# Sheet2.net
KiCad netlist of a schematic drawn in Altium Designer
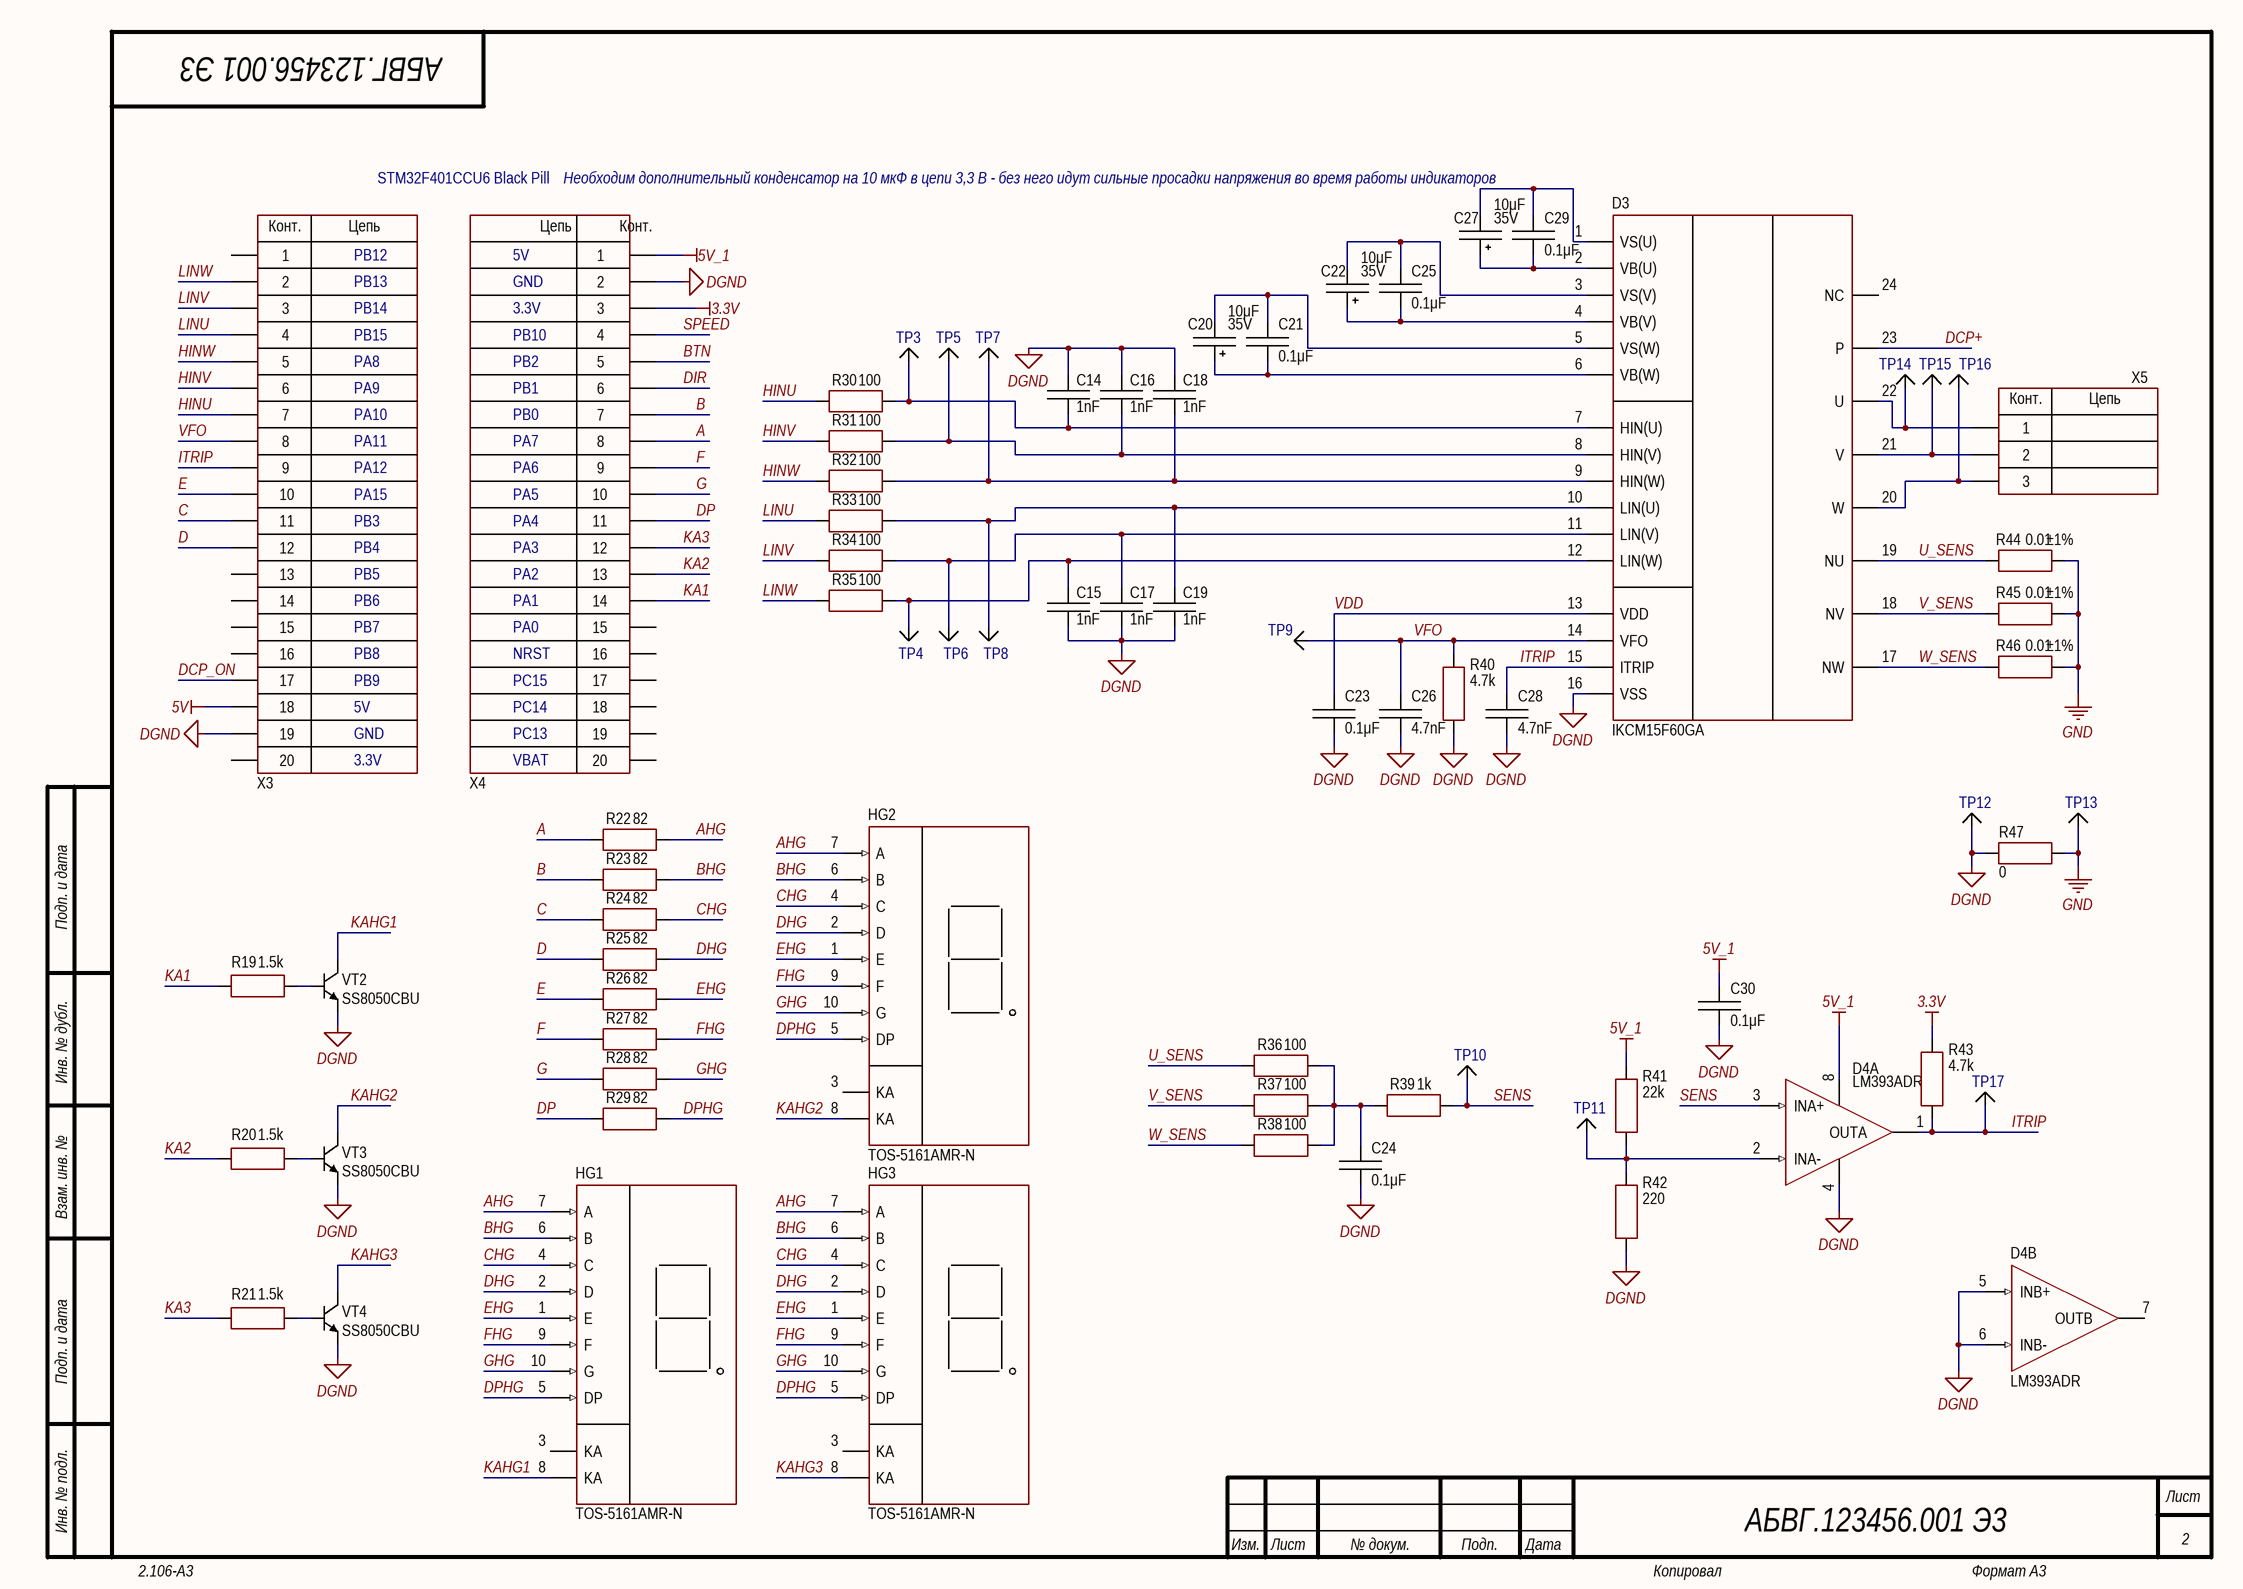
[diagram p0: Sheet2.SchDoc]

(export (version "E")
  (design (tool "Eeschema 10.0.6"))
  (components
    (comp (ref "C14")
      (value "1nF")
      (footprint "CAP: 1206")
      (fields
        (field (name "PARTNUMBER") "Ceramic capacitor, 1nF,   50V")
        (field (name "VALUEMANUFACTURERPARTNUMBER") "Ceramic capacitor, 1nF, X7R, ±10%, 50V, 1206, -55...+125°C")
        (field (name "TOLERANCE") "±10%")
      )
      (libsource (lib "capacitor") (part "Ceramic_1206"))
    )
    (comp (ref "C15")
      (value "1nF")
      (footprint "CAP: 1206")
      (fields
        (field (name "PARTNUMBER") "Ceramic capacitor, 1nF,   50V")
        (field (name "VALUEMANUFACTURERPARTNUMBER") "Ceramic capacitor, 1nF, X7R, ±10%, 50V, 1206, -55...+125°C")
        (field (name "TOLERANCE") "±10%")
      )
      (libsource (lib "capacitor") (part "Ceramic_1206"))
    )
    (comp (ref "C16")
      (value "1nF")
      (footprint "CAP: 1206")
      (fields
        (field (name "PARTNUMBER") "Ceramic capacitor, 1nF,   50V")
        (field (name "VALUEMANUFACTURERPARTNUMBER") "Ceramic capacitor, 1nF, X7R, ±10%, 50V, 1206, -55...+125°C")
        (field (name "TOLERANCE") "±10%")
      )
      (libsource (lib "capacitor") (part "Ceramic_1206"))
    )
    (comp (ref "C17")
      (value "1nF")
      (footprint "CAP: 1206")
      (fields
        (field (name "PARTNUMBER") "Ceramic capacitor, 1nF,   50V")
        (field (name "VALUEMANUFACTURERPARTNUMBER") "Ceramic capacitor, 1nF, X7R, ±10%, 50V, 1206, -55...+125°C")
        (field (name "TOLERANCE") "±10%")
      )
      (libsource (lib "capacitor") (part "Ceramic_1206"))
    )
    (comp (ref "C18")
      (value "1nF")
      (footprint "CAP: 1206")
      (fields
        (field (name "PARTNUMBER") "Ceramic capacitor, 1nF,   50V")
        (field (name "VALUEMANUFACTURERPARTNUMBER") "Ceramic capacitor, 1nF, X7R, ±10%, 50V, 1206, -55...+125°C")
        (field (name "TOLERANCE") "±10%")
      )
      (libsource (lib "capacitor") (part "Ceramic_1206"))
    )
    (comp (ref "C19")
      (value "1nF")
      (footprint "CAP: 1206")
      (fields
        (field (name "PARTNUMBER") "Ceramic capacitor, 1nF,   50V")
        (field (name "VALUEMANUFACTURERPARTNUMBER") "Ceramic capacitor, 1nF, X7R, ±10%, 50V, 1206, -55...+125°C")
        (field (name "TOLERANCE") "±10%")
      )
      (libsource (lib "capacitor") (part "Ceramic_1206"))
    )
    (comp (ref "C20")
      (value "10μF")
      (footprint "CAP: D5C2H11")
      (fields
        (field (name "MANUFACTURER") "?")
        (field (name "PARTNUMBER") "9000565842")
        (field (name "VALUEMANUFACTURERPARTNUMBER") "Aluminium capacitor, 10μF, 35V, ±20%, 54mOhm, ?, -40...+105°C")
        (field (name "VOLTAGE") "35V")
      )
      (libsource (lib "capacitor") (part "Aluminium"))
    )
    (comp (ref "C21")
      (value "0.1μF")
      (footprint "CAP: 1206")
      (fields
        (field (name "PARTNUMBER") "Ceramic capacitor, 0.1μF,   50V")
        (field (name "VALUEMANUFACTURERPARTNUMBER") "Ceramic capacitor, 0.1μF, X7R, ±10%, 50V, 1206, -55...+125°C")
        (field (name "TOLERANCE") "±10%")
      )
      (libsource (lib "capacitor") (part "Ceramic_1206"))
    )
    (comp (ref "C22")
      (value "10μF")
      (footprint "CAP: D5C2H11")
      (fields
        (field (name "MANUFACTURER") "?")
        (field (name "PARTNUMBER") "9000565842")
        (field (name "VALUEMANUFACTURERPARTNUMBER") "Aluminium capacitor, 10μF, 35V, ±20%, 54mOhm, ?, -40...+105°C")
        (field (name "VOLTAGE") "35V")
      )
      (libsource (lib "capacitor") (part "Aluminium"))
    )
    (comp (ref "C23")
      (value "0.1μF")
      (footprint "CAP: 1206")
      (fields
        (field (name "PARTNUMBER") "Ceramic capacitor, 0.1μF,   50V")
        (field (name "VALUEMANUFACTURERPARTNUMBER") "Ceramic capacitor, 0.1μF, X7R, ±10%, 50V, 1206, -55...+125°C")
        (field (name "TOLERANCE") "±10%")
      )
      (libsource (lib "capacitor") (part "Ceramic_1206"))
    )
    (comp (ref "C24")
      (value "0.1μF")
      (footprint "CAP: 1206")
      (fields
        (field (name "PARTNUMBER") "Ceramic capacitor, 0.1μF,   50V")
        (field (name "VALUEMANUFACTURERPARTNUMBER") "Ceramic capacitor, 0.1μF, X7R, ±10%, 50V, 1206, -55...+125°C")
        (field (name "TOLERANCE") "±10%")
      )
      (libsource (lib "capacitor") (part "Ceramic_1206"))
    )
    (comp (ref "C25")
      (value "0.1μF")
      (footprint "CAP: 1206")
      (fields
        (field (name "PARTNUMBER") "Ceramic capacitor, 0.1μF,   50V")
        (field (name "VALUEMANUFACTURERPARTNUMBER") "Ceramic capacitor, 0.1μF, X7R, ±10%, 50V, 1206, -55...+125°C")
        (field (name "TOLERANCE") "±10%")
      )
      (libsource (lib "capacitor") (part "Ceramic_1206"))
    )
    (comp (ref "C26")
      (value "4.7nF")
      (footprint "CAP: 1206")
      (fields
        (field (name "PARTNUMBER") "Ceramic capacitor, 4.7nF,   50V")
        (field (name "VALUEMANUFACTURERPARTNUMBER") "Ceramic capacitor, 4.7nF, X7R, ±10%, 50V, 1206, -55...+125°C")
        (field (name "TOLERANCE") "±10%")
      )
      (libsource (lib "capacitor") (part "Ceramic_1206"))
    )
    (comp (ref "C27")
      (value "10μF")
      (footprint "CAP: D5C2H11")
      (fields
        (field (name "MANUFACTURER") "?")
        (field (name "PARTNUMBER") "9000565842")
        (field (name "VALUEMANUFACTURERPARTNUMBER") "Aluminium capacitor, 10μF, 35V, ±20%, 54mOhm, ?, -40...+105°C")
        (field (name "VOLTAGE") "35V")
      )
      (libsource (lib "capacitor") (part "Aluminium"))
    )
    (comp (ref "C28")
      (value "4.7nF")
      (footprint "CAP: 1206")
      (fields
        (field (name "PARTNUMBER") "Ceramic capacitor, 4.7nF,   50V")
        (field (name "VALUEMANUFACTURERPARTNUMBER") "Ceramic capacitor, 4.7nF, X7R, ±10%, 50V, 1206, -55...+125°C")
        (field (name "TOLERANCE") "±10%")
      )
      (libsource (lib "capacitor") (part "Ceramic_1206"))
    )
    (comp (ref "C29")
      (value "0.1μF")
      (footprint "CAP: 1206")
      (fields
        (field (name "PARTNUMBER") "Ceramic capacitor, 0.1μF,   50V")
        (field (name "VALUEMANUFACTURERPARTNUMBER") "Ceramic capacitor, 0.1μF, X7R, ±10%, 50V, 1206, -55...+125°C")
        (field (name "TOLERANCE") "±10%")
      )
      (libsource (lib "capacitor") (part "Ceramic_1206"))
    )
    (comp (ref "C30")
      (value "0.1μF")
      (footprint "CAP: 1206")
      (fields
        (field (name "PARTNUMBER") "Ceramic capacitor, 0.1μF,   50V")
        (field (name "VALUEMANUFACTURERPARTNUMBER") "Ceramic capacitor, 0.1μF, X7R, ±10%, 50V, 1206, -55...+125°C")
        (field (name "TOLERANCE") "±10%")
      )
      (libsource (lib "capacitor") (part "Ceramic_1206"))
    )
    (comp (ref "D3")
      (value "~")
      (footprint "INF-CIPOS MINI")
      (description "Fully isolated Dual In-Line molded  IGBT module")
      (fields
        (field (name "MANUFACTURER") "INFINEON TECHNOLOGIES AG.")
        (field (name "VALUEMANUFACTURERPARTNUMBER") "600 V, 15 A three-phase intelligent power module, , , 15A, , 450V, -40...+125°C, IKCM15F60GA")
        (field (name "PARTNUMBER") "IKCM15F60GA")
      )
      (libsource (lib "ic-power-module") (part "IKCM15F60GA"))
    )
    (comp (ref "D4")
      (value "~")
      (footprint "8-SOIC")
      (description "Low Power Low Offset Voltage Dual Comparator")
      (fields
        (field (name "MANUFACTURER") "Maxim Integrated Products")
        (field (name "VALUEMANUFACTURERPARTNUMBER") "IC comparator, Rail-to-Rail, 2...36 V, ±1...±18 V, 0…70°C, SOP-8")
        (field (name "PARTNUMBER") "LM393ADR")
      )
      (libsource (lib "ic-comparator") (part "LM393ADR"))
    )
    (comp (ref "HG1")
      (value "~")
      (footprint "TOS-5161AMR-N")
      (description "Single Digit Display LED")
      (fields
        (field (name "MANUFACTURER") "Taiwan Oasis Technology Co., Ltd")
        (field (name "VALUEMANUFACTURERPARTNUMBER") "Single Digit Display LED, , -25...+85°C, TOS-5161AMR-N")
        (field (name "PARTNUMBER") "TOS-5161AMR-N")
      )
      (libsource (lib "indicator") (part "TOS-5161AMR-N"))
    )
    (comp (ref "HG2")
      (value "~")
      (footprint "TOS-5161AMR-N")
      (description "Single Digit Display LED")
      (fields
        (field (name "MANUFACTURER") "Taiwan Oasis Technology Co., Ltd")
        (field (name "VALUEMANUFACTURERPARTNUMBER") "Single Digit Display LED, , -25...+85°C, TOS-5161AMR-N")
        (field (name "PARTNUMBER") "TOS-5161AMR-N")
      )
      (libsource (lib "indicator") (part "TOS-5161AMR-N"))
    )
    (comp (ref "HG3")
      (value "~")
      (footprint "TOS-5161AMR-N")
      (description "Single Digit Display LED")
      (fields
        (field (name "MANUFACTURER") "Taiwan Oasis Technology Co., Ltd")
        (field (name "VALUEMANUFACTURERPARTNUMBER") "Single Digit Display LED, , -25...+85°C, TOS-5161AMR-N")
        (field (name "PARTNUMBER") "TOS-5161AMR-N")
      )
      (libsource (lib "indicator") (part "TOS-5161AMR-N"))
    )
    (comp (ref "R19")
      (value "1.5k")
      (footprint "RES: 1206")
      (fields
        (field (name "MANUFACTURER") "Yageo")
        (field (name "PARTNUMBER") "RC1206JR-07100RL")
        (field (name "VALUEMANUFACTURERPARTNUMBER") "Resistor film, 1.5k, ±5%, 1206, 0.25W, -55...+125°C")
      )
      (libsource (lib "resistor") (part "Resistor_1206"))
    )
    (comp (ref "R20")
      (value "1.5k")
      (footprint "RES: 1206")
      (fields
        (field (name "MANUFACTURER") "Yageo")
        (field (name "PARTNUMBER") "RC1206JR-07100RL")
        (field (name "VALUEMANUFACTURERPARTNUMBER") "Resistor film, 1.5k, ±5%, 1206, 0.25W, -55...+125°C")
      )
      (libsource (lib "resistor") (part "Resistor_1206"))
    )
    (comp (ref "R21")
      (value "1.5k")
      (footprint "RES: 1206")
      (fields
        (field (name "MANUFACTURER") "Yageo")
        (field (name "PARTNUMBER") "RC1206JR-07100RL")
        (field (name "VALUEMANUFACTURERPARTNUMBER") "Resistor film, 1.5k, ±5%, 1206, 0.25W, -55...+125°C")
      )
      (libsource (lib "resistor") (part "Resistor_1206"))
    )
    (comp (ref "R22")
      (value "82")
      (footprint "RES: 1206")
      (fields
        (field (name "MANUFACTURER") "Yageo")
        (field (name "PARTNUMBER") "RC1206JR-07100RL")
        (field (name "VALUEMANUFACTURERPARTNUMBER") "Resistor film, 82, ±5%, 1206, 0.25W, -55...+125°C")
      )
      (libsource (lib "resistor") (part "Resistor_1206"))
    )
    (comp (ref "R23")
      (value "82")
      (footprint "RES: 1206")
      (fields
        (field (name "MANUFACTURER") "Yageo")
        (field (name "PARTNUMBER") "RC1206JR-07100RL")
        (field (name "VALUEMANUFACTURERPARTNUMBER") "Resistor film, 82, ±5%, 1206, 0.25W, -55...+125°C")
      )
      (libsource (lib "resistor") (part "Resistor_1206"))
    )
    (comp (ref "R24")
      (value "82")
      (footprint "RES: 1206")
      (fields
        (field (name "MANUFACTURER") "Yageo")
        (field (name "PARTNUMBER") "RC1206JR-07100RL")
        (field (name "VALUEMANUFACTURERPARTNUMBER") "Resistor film, 82, ±5%, 1206, 0.25W, -55...+125°C")
      )
      (libsource (lib "resistor") (part "Resistor_1206"))
    )
    (comp (ref "R25")
      (value "82")
      (footprint "RES: 1206")
      (fields
        (field (name "MANUFACTURER") "Yageo")
        (field (name "PARTNUMBER") "RC1206JR-07100RL")
        (field (name "VALUEMANUFACTURERPARTNUMBER") "Resistor film, 82, ±5%, 1206, 0.25W, -55...+125°C")
      )
      (libsource (lib "resistor") (part "Resistor_1206"))
    )
    (comp (ref "R26")
      (value "82")
      (footprint "RES: 1206")
      (fields
        (field (name "MANUFACTURER") "Yageo")
        (field (name "PARTNUMBER") "RC1206JR-07100RL")
        (field (name "VALUEMANUFACTURERPARTNUMBER") "Resistor film, 82, ±5%, 1206, 0.25W, -55...+125°C")
      )
      (libsource (lib "resistor") (part "Resistor_1206"))
    )
    (comp (ref "R27")
      (value "82")
      (footprint "RES: 1206")
      (fields
        (field (name "MANUFACTURER") "Yageo")
        (field (name "PARTNUMBER") "RC1206JR-07100RL")
        (field (name "VALUEMANUFACTURERPARTNUMBER") "Resistor film, 82, ±5%, 1206, 0.25W, -55...+125°C")
      )
      (libsource (lib "resistor") (part "Resistor_1206"))
    )
    (comp (ref "R28")
      (value "82")
      (footprint "RES: 1206")
      (fields
        (field (name "MANUFACTURER") "Yageo")
        (field (name "PARTNUMBER") "RC1206JR-07100RL")
        (field (name "VALUEMANUFACTURERPARTNUMBER") "Resistor film, 82, ±5%, 1206, 0.25W, -55...+125°C")
      )
      (libsource (lib "resistor") (part "Resistor_1206"))
    )
    (comp (ref "R29")
      (value "82")
      (footprint "RES: 1206")
      (fields
        (field (name "MANUFACTURER") "Yageo")
        (field (name "PARTNUMBER") "RC1206JR-07100RL")
        (field (name "VALUEMANUFACTURERPARTNUMBER") "Resistor film, 82, ±5%, 1206, 0.25W, -55...+125°C")
      )
      (libsource (lib "resistor") (part "Resistor_1206"))
    )
    (comp (ref "R30")
      (value "100")
      (footprint "RES: 1206")
      (fields
        (field (name "MANUFACTURER") "Yageo")
        (field (name "PARTNUMBER") "RC1206JR-07100RL")
        (field (name "VALUEMANUFACTURERPARTNUMBER") "Resistor film, 100, ±5%, 1206, 0.25W, -55...+125°C")
      )
      (libsource (lib "resistor") (part "Resistor_1206"))
    )
    (comp (ref "R31")
      (value "100")
      (footprint "RES: 1206")
      (fields
        (field (name "MANUFACTURER") "Yageo")
        (field (name "PARTNUMBER") "RC1206JR-07100RL")
        (field (name "VALUEMANUFACTURERPARTNUMBER") "Resistor film, 100, ±5%, 1206, 0.25W, -55...+125°C")
      )
      (libsource (lib "resistor") (part "Resistor_1206"))
    )
    (comp (ref "R32")
      (value "100")
      (footprint "RES: 1206")
      (fields
        (field (name "MANUFACTURER") "Yageo")
        (field (name "PARTNUMBER") "RC1206JR-07100RL")
        (field (name "VALUEMANUFACTURERPARTNUMBER") "Resistor film, 100, ±5%, 1206, 0.25W, -55...+125°C")
      )
      (libsource (lib "resistor") (part "Resistor_1206"))
    )
    (comp (ref "R33")
      (value "100")
      (footprint "RES: 1206")
      (fields
        (field (name "MANUFACTURER") "Yageo")
        (field (name "PARTNUMBER") "RC1206JR-07100RL")
        (field (name "VALUEMANUFACTURERPARTNUMBER") "Resistor film, 100, ±5%, 1206, 0.25W, -55...+125°C")
      )
      (libsource (lib "resistor") (part "Resistor_1206"))
    )
    (comp (ref "R34")
      (value "100")
      (footprint "RES: 1206")
      (fields
        (field (name "MANUFACTURER") "Yageo")
        (field (name "PARTNUMBER") "RC1206JR-07100RL")
        (field (name "VALUEMANUFACTURERPARTNUMBER") "Resistor film, 100, ±5%, 1206, 0.25W, -55...+125°C")
      )
      (libsource (lib "resistor") (part "Resistor_1206"))
    )
    (comp (ref "R35")
      (value "100")
      (footprint "RES: 1206")
      (fields
        (field (name "MANUFACTURER") "Yageo")
        (field (name "PARTNUMBER") "RC1206JR-07100RL")
        (field (name "VALUEMANUFACTURERPARTNUMBER") "Resistor film, 100, ±5%, 1206, 0.25W, -55...+125°C")
      )
      (libsource (lib "resistor") (part "Resistor_1206"))
    )
    (comp (ref "R36")
      (value "100")
      (footprint "RES: 1206")
      (fields
        (field (name "MANUFACTURER") "Yageo")
        (field (name "PARTNUMBER") "RC1206JR-07100RL")
        (field (name "VALUEMANUFACTURERPARTNUMBER") "Resistor film, 100, ±5%, 1206, 0.25W, -55...+125°C")
      )
      (libsource (lib "resistor") (part "Resistor_1206"))
    )
    (comp (ref "R37")
      (value "100")
      (footprint "RES: 1206")
      (fields
        (field (name "MANUFACTURER") "Yageo")
        (field (name "PARTNUMBER") "RC1206JR-07100RL")
        (field (name "VALUEMANUFACTURERPARTNUMBER") "Resistor film, 100, ±5%, 1206, 0.25W, -55...+125°C")
      )
      (libsource (lib "resistor") (part "Resistor_1206"))
    )
    (comp (ref "R38")
      (value "100")
      (footprint "RES: 1206")
      (fields
        (field (name "MANUFACTURER") "Yageo")
        (field (name "PARTNUMBER") "RC1206JR-07100RL")
        (field (name "VALUEMANUFACTURERPARTNUMBER") "Resistor film, 100, ±5%, 1206, 0.25W, -55...+125°C")
      )
      (libsource (lib "resistor") (part "Resistor_1206"))
    )
    (comp (ref "R39")
      (value "1k")
      (footprint "RES: 1206")
      (fields
        (field (name "MANUFACTURER") "Yageo")
        (field (name "PARTNUMBER") "RC1206JR-07100RL")
        (field (name "VALUEMANUFACTURERPARTNUMBER") "Resistor film, 1k, ±5%, 1206, 0.25W, -55...+125°C")
      )
      (libsource (lib "resistor") (part "Resistor_1206"))
    )
    (comp (ref "R40")
      (value "4.7k")
      (footprint "RES: 1206")
      (fields
        (field (name "MANUFACTURER") "Yageo")
        (field (name "PARTNUMBER") "RC1206JR-07100RL")
        (field (name "VALUEMANUFACTURERPARTNUMBER") "Resistor film, 4.7k, ±5%, 1206, 0.25W, -55...+125°C")
      )
      (libsource (lib "") (part "Resistor_1206_1"))
    )
    (comp (ref "R41")
      (value "22k")
      (footprint "RES: 1206")
      (fields
        (field (name "MANUFACTURER") "Yageo")
        (field (name "PARTNUMBER") "RC1206JR-07100RL")
        (field (name "VALUEMANUFACTURERPARTNUMBER") "Resistor film, 22k, ±5%, 1206, 0.25W, -55...+125°C")
      )
      (libsource (lib "") (part "Resistor_1206_1"))
    )
    (comp (ref "R42")
      (value "220")
      (footprint "RES: 1206")
      (fields
        (field (name "MANUFACTURER") "Yageo")
        (field (name "PARTNUMBER") "RC1206JR-07100RL")
        (field (name "VALUEMANUFACTURERPARTNUMBER") "Resistor film, 220, ±5%, 1206, 0.25W, -55...+125°C")
      )
      (libsource (lib "") (part "Resistor_1206_1"))
    )
    (comp (ref "R43")
      (value "4.7k")
      (footprint "RES: 1206")
      (fields
        (field (name "MANUFACTURER") "Yageo")
        (field (name "PARTNUMBER") "RC1206JR-07100RL")
        (field (name "VALUEMANUFACTURERPARTNUMBER") "Resistor film, 4.7k, ±5%, 1206, 0.25W, -55...+125°C")
      )
      (libsource (lib "") (part "Resistor_1206_1"))
    )
    (comp (ref "R44")
      (value "0.01")
      (footprint "RES: 2512")
      (fields
        (field (name "MANUFACTURER") "UNI-ROYAL(Uniroyal Elec)")
        (field (name "PARTNUMBER") "25121WF100MT4E")
        (field (name "VALUEMANUFACTURERPARTNUMBER") "Resistor film, 0.01, ±1%, 2512, 1W, -55...+125°C")
        (field (name "TOLERANCE") "±1%")
      )
      (libsource (lib "resistor") (part "Resistor_2512"))
    )
    (comp (ref "R45")
      (value "0.01")
      (footprint "RES: 2512")
      (fields
        (field (name "MANUFACTURER") "UNI-ROYAL(Uniroyal Elec)")
        (field (name "PARTNUMBER") "25121WF100MT4E")
        (field (name "VALUEMANUFACTURERPARTNUMBER") "Resistor film, 0.01, ±1%, 2512, 1W, -55...+125°C")
        (field (name "TOLERANCE") "±1%")
      )
      (libsource (lib "resistor") (part "Resistor_2512"))
    )
    (comp (ref "R46")
      (value "0.01")
      (footprint "RES: 2512")
      (fields
        (field (name "MANUFACTURER") "UNI-ROYAL(Uniroyal Elec)")
        (field (name "PARTNUMBER") "25121WF100MT4E")
        (field (name "VALUEMANUFACTURERPARTNUMBER") "Resistor film, 0.01, ±1%, 2512, 1W, -55...+125°C")
        (field (name "TOLERANCE") "±1%")
      )
      (libsource (lib "resistor") (part "Resistor_2512"))
    )
    (comp (ref "R47")
      (value "0")
      (footprint "RES: 1206")
      (fields
        (field (name "MANUFACTURER") "Yageo")
        (field (name "PARTNUMBER") "RC1206JR-07100RL")
        (field (name "VALUEMANUFACTURERPARTNUMBER") "Resistor film, 0, ±5%, 1206, 0.25W, -55...+125°C")
      )
      (libsource (lib "") (part "Resistor_1206_2"))
    )
    (comp (ref "TP3")
      (value "Test_Point")
      (footprint "TEST POINT KEYSTONE")
      (libsource (lib "other") (part "Test_Point"))
    )
    (comp (ref "TP4")
      (value "Test_Point")
      (footprint "TEST POINT KEYSTONE")
      (libsource (lib "other") (part "Test_Point"))
    )
    (comp (ref "TP5")
      (value "Test_Point")
      (footprint "TEST POINT KEYSTONE")
      (libsource (lib "other") (part "Test_Point"))
    )
    (comp (ref "TP6")
      (value "Test_Point")
      (footprint "TEST POINT KEYSTONE")
      (libsource (lib "other") (part "Test_Point"))
    )
    (comp (ref "TP7")
      (value "Test_Point")
      (footprint "TEST POINT KEYSTONE")
      (libsource (lib "other") (part "Test_Point"))
    )
    (comp (ref "TP8")
      (value "Test_Point")
      (footprint "TEST POINT KEYSTONE")
      (libsource (lib "other") (part "Test_Point"))
    )
    (comp (ref "TP9")
      (value "Test_Point")
      (footprint "TEST POINT KEYSTONE")
      (libsource (lib "other") (part "Test_Point"))
    )
    (comp (ref "TP10")
      (value "Test_Point")
      (footprint "TEST POINT KEYSTONE")
      (libsource (lib "other") (part "Test_Point"))
    )
    (comp (ref "TP11")
      (value "Test_Point")
      (footprint "TEST POINT KEYSTONE")
      (libsource (lib "other") (part "Test_Point"))
    )
    (comp (ref "TP12")
      (value "Test_Point")
      (footprint "TEST POINT KEYSTONE")
      (libsource (lib "other") (part "Test_Point"))
    )
    (comp (ref "TP13")
      (value "Test_Point")
      (footprint "TEST POINT KEYSTONE")
      (libsource (lib "other") (part "Test_Point"))
    )
    (comp (ref "TP14")
      (value "Test_Point")
      (footprint "TEST POINT KEYSTONE")
      (libsource (lib "other") (part "Test_Point"))
    )
    (comp (ref "TP15")
      (value "Test_Point")
      (footprint "TEST POINT KEYSTONE")
      (libsource (lib "other") (part "Test_Point"))
    )
    (comp (ref "TP16")
      (value "Test_Point")
      (footprint "TEST POINT KEYSTONE")
      (libsource (lib "other") (part "Test_Point"))
    )
    (comp (ref "TP17")
      (value "Test_Point")
      (footprint "TEST POINT KEYSTONE")
      (libsource (lib "other") (part "Test_Point"))
    )
    (comp (ref "VT2")
      (value "~")
      (footprint "TO-92 - formed leads")
      (fields
        (field (name "MANUFACTURER") "ON Semiconductor")
        (field (name "VALUEMANUFACTURERPARTNUMBER") "NPN transistor, 40V, 1.5A, 190MHz, 1W, 0.5Vmax, 120...200, TO-92, 150°C")
        (field (name "PARTNUMBER") "SS8050CBU")
      )
      (libsource (lib "transistor") (part "SS8050CBU"))
    )
    (comp (ref "VT3")
      (value "~")
      (footprint "TO-92 - formed leads")
      (fields
        (field (name "MANUFACTURER") "ON Semiconductor")
        (field (name "VALUEMANUFACTURERPARTNUMBER") "NPN transistor, 40V, 1.5A, 190MHz, 1W, 0.5Vmax, 120...200, TO-92, 150°C")
        (field (name "PARTNUMBER") "SS8050CBU")
      )
      (libsource (lib "transistor") (part "SS8050CBU"))
    )
    (comp (ref "VT4")
      (value "~")
      (footprint "TO-92 - formed leads")
      (fields
        (field (name "MANUFACTURER") "ON Semiconductor")
        (field (name "VALUEMANUFACTURERPARTNUMBER") "NPN transistor, 40V, 1.5A, 190MHz, 1W, 0.5Vmax, 120...200, TO-92, 150°C")
        (field (name "PARTNUMBER") "SS8050CBU")
      )
      (libsource (lib "transistor") (part "SS8050CBU"))
    )
    (comp (ref "X3")
      (value "~")
      (footprint "PBS-20 narrow pitch")
      (fields
        (field (name "MANUFACTURER") "Connfly")
        (field (name "VALUEMANUFACTURERPARTNUMBER") "Connector, 20pin, 2.54mm, 500VAC, 3A")
        (field (name "PARTNUMBER") "PBS-20")
      )
      (libsource (lib "connector") (part "PBS-20"))
    )
    (comp (ref "X4")
      (value "~")
      (footprint "PBS-20 narrow pitch")
      (fields
        (field (name "MANUFACTURER") "Connfly")
        (field (name "VALUEMANUFACTURERPARTNUMBER") "Connector, 20pin, 2.54mm, 500VAC, 3A")
        (field (name "PARTNUMBER") "PBS-20")
      )
      (libsource (lib "") (part "PBS-20_1"))
    )
    (comp (ref "X5")
      (value "~")
      (footprint "DG128-7.5-03P")
      (fields
        (field (name "MANUFACTURER") "Degson Electronics")
        (field (name "VALUEMANUFACTURERPARTNUMBER") "Connector, 3pin, 9.53mm, 300VAC, 16A")
        (field (name "PARTNUMBER") "DG128-7.5-03P-14")
      )
      (libsource (lib "connector") (part "DG128-7.5-03P-14"))
    )
  )
  (nets
    (net (code "1") (name "/A") (class "Default")
      (node (ref "R22") (pin "1") (pinfunction "1_1") (pintype "passive"))
      (node (ref "X4") (pin "8") (pinfunction "8_8") (pintype "power_in"))
    )
    (net (code "2") (name "/AHG") (class "Default")
      (node (ref "HG1") (pin "7") (pinfunction "A_7") (pintype "input"))
      (node (ref "HG2") (pin "7") (pinfunction "A_7") (pintype "input"))
      (node (ref "HG3") (pin "7") (pinfunction "A_7") (pintype "input"))
      (node (ref "R22") (pin "2") (pinfunction "2_2") (pintype "passive"))
    )
    (net (code "3") (name "/B") (class "Default")
      (node (ref "R23") (pin "1") (pinfunction "1_1") (pintype "passive"))
      (node (ref "X4") (pin "7") (pinfunction "7_7") (pintype "power_in"))
    )
    (net (code "4") (name "/BHG") (class "Default")
      (node (ref "HG1") (pin "6") (pinfunction "B_6") (pintype "input"))
      (node (ref "HG2") (pin "6") (pinfunction "B_6") (pintype "input"))
      (node (ref "HG3") (pin "6") (pinfunction "B_6") (pintype "input"))
      (node (ref "R23") (pin "2") (pinfunction "2_2") (pintype "passive"))
    )
    (net (code "5") (name "/BTN") (class "Default")
      (node (ref "X4") (pin "5") (pinfunction "5_5") (pintype "power_in"))
    )
    (net (code "6") (name "/C") (class "Default")
      (node (ref "R24") (pin "1") (pinfunction "1_1") (pintype "passive"))
      (node (ref "X3") (pin "11") (pinfunction "11_11") (pintype "power_in"))
    )
    (net (code "7") (name "/CHG") (class "Default")
      (node (ref "HG1") (pin "4") (pinfunction "C_4") (pintype "input"))
      (node (ref "HG2") (pin "4") (pinfunction "C_4") (pintype "input"))
      (node (ref "HG3") (pin "4") (pinfunction "C_4") (pintype "input"))
      (node (ref "R24") (pin "2") (pinfunction "2_2") (pintype "passive"))
    )
    (net (code "8") (name "/D") (class "Default")
      (node (ref "R25") (pin "1") (pinfunction "1_1") (pintype "passive"))
      (node (ref "X3") (pin "12") (pinfunction "12_12") (pintype "power_in"))
    )
    (net (code "9") (name "/DCP+") (class "Default")
      (node (ref "D3") (pin "23") (pinfunction "P_23") (pintype "passive"))
    )
    (net (code "10") (name "/DCP_ON") (class "Default")
      (node (ref "X3") (pin "17") (pinfunction "17_17") (pintype "power_in"))
    )
    (net (code "11") (name "/DHG") (class "Default")
      (node (ref "HG1") (pin "2") (pinfunction "D_2") (pintype "input"))
      (node (ref "HG2") (pin "2") (pinfunction "D_2") (pintype "input"))
      (node (ref "HG3") (pin "2") (pinfunction "D_2") (pintype "input"))
      (node (ref "R25") (pin "2") (pinfunction "2_2") (pintype "passive"))
    )
    (net (code "12") (name "/DIR") (class "Default")
      (node (ref "X4") (pin "6") (pinfunction "6_6") (pintype "power_in"))
    )
    (net (code "13") (name "/DP") (class "Default")
      (node (ref "R29") (pin "1") (pinfunction "1_1") (pintype "passive"))
      (node (ref "X4") (pin "11") (pinfunction "11_11") (pintype "power_in"))
    )
    (net (code "14") (name "/DPHG") (class "Default")
      (node (ref "HG1") (pin "5") (pinfunction "DP_5") (pintype "input"))
      (node (ref "HG2") (pin "5") (pinfunction "DP_5") (pintype "input"))
      (node (ref "HG3") (pin "5") (pinfunction "DP_5") (pintype "input"))
      (node (ref "R29") (pin "2") (pinfunction "2_2") (pintype "passive"))
    )
    (net (code "15") (name "/E") (class "Default")
      (node (ref "R26") (pin "1") (pinfunction "1_1") (pintype "passive"))
      (node (ref "X3") (pin "10") (pinfunction "10_10") (pintype "power_in"))
    )
    (net (code "16") (name "/EHG") (class "Default")
      (node (ref "HG1") (pin "1") (pinfunction "E_1") (pintype "input"))
      (node (ref "HG2") (pin "1") (pinfunction "E_1") (pintype "input"))
      (node (ref "HG3") (pin "1") (pinfunction "E_1") (pintype "input"))
      (node (ref "R26") (pin "2") (pinfunction "2_2") (pintype "passive"))
    )
    (net (code "17") (name "/F") (class "Default")
      (node (ref "R27") (pin "1") (pinfunction "1_1") (pintype "passive"))
      (node (ref "X4") (pin "9") (pinfunction "9_9") (pintype "power_in"))
    )
    (net (code "18") (name "/FHG") (class "Default")
      (node (ref "HG1") (pin "9") (pinfunction "F_9") (pintype "input"))
      (node (ref "HG2") (pin "9") (pinfunction "F_9") (pintype "input"))
      (node (ref "HG3") (pin "9") (pinfunction "F_9") (pintype "input"))
      (node (ref "R27") (pin "2") (pinfunction "2_2") (pintype "passive"))
    )
    (net (code "19") (name "/G") (class "Default")
      (node (ref "R28") (pin "1") (pinfunction "1_1") (pintype "passive"))
      (node (ref "X4") (pin "10") (pinfunction "10_10") (pintype "power_in"))
    )
    (net (code "20") (name "/GHG") (class "Default")
      (node (ref "HG1") (pin "10") (pinfunction "G_10") (pintype "input"))
      (node (ref "HG2") (pin "10") (pinfunction "G_10") (pintype "input"))
      (node (ref "HG3") (pin "10") (pinfunction "G_10") (pintype "input"))
      (node (ref "R28") (pin "2") (pinfunction "2_2") (pintype "passive"))
    )
    (net (code "21") (name "/HINU") (class "Default")
      (node (ref "R30") (pin "1") (pinfunction "1_1") (pintype "passive"))
      (node (ref "X3") (pin "7") (pinfunction "7_7") (pintype "power_in"))
    )
    (net (code "22") (name "/HINV") (class "Default")
      (node (ref "R31") (pin "1") (pinfunction "1_1") (pintype "passive"))
      (node (ref "X3") (pin "6") (pinfunction "6_6") (pintype "power_in"))
    )
    (net (code "23") (name "/HINW") (class "Default")
      (node (ref "R32") (pin "1") (pinfunction "1_1") (pintype "passive"))
      (node (ref "X3") (pin "5") (pinfunction "5_5") (pintype "power_in"))
    )
    (net (code "24") (name "/ITRIP") (class "Default")
      (node (ref "C28") (pin "2") (pinfunction "2_2") (pintype "passive"))
      (node (ref "D3") (pin "15") (pinfunction "ITRIP_15") (pintype "passive"))
      (node (ref "D4") (pin "1") (pinfunction "OUTA_1") (pintype "power_in"))
      (node (ref "R43") (pin "1") (pinfunction "1_1") (pintype "passive"))
      (node (ref "TP17") (pin "1") (pinfunction "1_1") (pintype "passive"))
      (node (ref "X3") (pin "9") (pinfunction "9_9") (pintype "power_in"))
    )
    (net (code "25") (name "/KA1") (class "Default")
      (node (ref "R19") (pin "1") (pinfunction "1_1") (pintype "passive"))
      (node (ref "X4") (pin "14") (pinfunction "14_14") (pintype "power_in"))
    )
    (net (code "26") (name "/KA2") (class "Default")
      (node (ref "R20") (pin "1") (pinfunction "1_1") (pintype "passive"))
      (node (ref "X4") (pin "13") (pinfunction "13_13") (pintype "power_in"))
    )
    (net (code "27") (name "/KA3") (class "Default")
      (node (ref "R21") (pin "1") (pinfunction "1_1") (pintype "passive"))
      (node (ref "X4") (pin "12") (pinfunction "12_12") (pintype "power_in"))
    )
    (net (code "28") (name "/KAHG1") (class "Default")
      (node (ref "HG1") (pin "8") (pinfunction "KA_8") (pintype "passive"))
      (node (ref "VT2") (pin "3") (pinfunction "C_3") (pintype "passive"))
    )
    (net (code "29") (name "/KAHG2") (class "Default")
      (node (ref "HG2") (pin "8") (pinfunction "KA_8") (pintype "passive"))
      (node (ref "VT3") (pin "3") (pinfunction "C_3") (pintype "passive"))
    )
    (net (code "30") (name "/KAHG3") (class "Default")
      (node (ref "HG3") (pin "8") (pinfunction "KA_8") (pintype "passive"))
      (node (ref "VT4") (pin "3") (pinfunction "C_3") (pintype "passive"))
    )
    (net (code "31") (name "/LINU") (class "Default")
      (node (ref "R33") (pin "1") (pinfunction "1_1") (pintype "passive"))
      (node (ref "X3") (pin "4") (pinfunction "4_4") (pintype "power_in"))
    )
    (net (code "32") (name "/LINV") (class "Default")
      (node (ref "R34") (pin "1") (pinfunction "1_1") (pintype "passive"))
      (node (ref "X3") (pin "3") (pinfunction "3_3") (pintype "power_in"))
    )
    (net (code "33") (name "/LINW") (class "Default")
      (node (ref "R35") (pin "1") (pinfunction "1_1") (pintype "passive"))
      (node (ref "X3") (pin "2") (pinfunction "2_2") (pintype "passive"))
    )
    (net (code "34") (name "/SENS") (class "Default")
      (node (ref "D4") (pin "3") (pinfunction "INA+_3") (pintype "input"))
      (node (ref "R39") (pin "2") (pinfunction "2_2") (pintype "passive"))
      (node (ref "TP10") (pin "1") (pinfunction "1_1") (pintype "passive"))
    )
    (net (code "35") (name "/SPEED") (class "Default")
      (node (ref "X4") (pin "4") (pinfunction "4_4") (pintype "power_in"))
    )
    (net (code "36") (name "/U_SENS") (class "Default")
      (node (ref "D3") (pin "19") (pinfunction "NU_19") (pintype "passive"))
      (node (ref "R36") (pin "1") (pinfunction "1_1") (pintype "passive"))
      (node (ref "R44") (pin "1") (pinfunction "1_1") (pintype "passive"))
    )
    (net (code "37") (name "/VDD") (class "Default")
      (node (ref "C23") (pin "2") (pinfunction "2_2") (pintype "passive"))
      (node (ref "D3") (pin "13") (pinfunction "VDD_13") (pintype "passive"))
    )
    (net (code "38") (name "/VFO") (class "Default")
      (node (ref "C26") (pin "2") (pinfunction "2_2") (pintype "passive"))
      (node (ref "D3") (pin "14") (pinfunction "VFO_14") (pintype "passive"))
      (node (ref "R40") (pin "2") (pinfunction "2_2") (pintype "passive"))
      (node (ref "TP9") (pin "1") (pinfunction "1_1") (pintype "passive"))
      (node (ref "X3") (pin "8") (pinfunction "8_8") (pintype "power_in"))
    )
    (net (code "39") (name "/V_SENS") (class "Default")
      (node (ref "D3") (pin "18") (pinfunction "NV_18") (pintype "passive"))
      (node (ref "R37") (pin "1") (pinfunction "1_1") (pintype "passive"))
      (node (ref "R45") (pin "1") (pinfunction "1_1") (pintype "passive"))
    )
    (net (code "40") (name "/W_SENS") (class "Default")
      (node (ref "D3") (pin "17") (pinfunction "NW_17") (pintype "passive"))
      (node (ref "R38") (pin "1") (pinfunction "1_1") (pintype "passive"))
      (node (ref "R46") (pin "1") (pinfunction "1_1") (pintype "passive"))
    )
    (net (code "41") (name "3.3V") (class "Default")
      (node (ref "R43") (pin "2") (pinfunction "2_2") (pintype "passive"))
      (node (ref "X4") (pin "3") (pinfunction "3_3") (pintype "power_in"))
    )
    (net (code "42") (name "5V") (class "Default")
      (node (ref "X3") (pin "18") (pinfunction "18_18") (pintype "power_in"))
    )
    (net (code "43") (name "5V_1") (class "Default")
      (node (ref "C30") (pin "2") (pinfunction "2_2") (pintype "passive"))
      (node (ref "D4") (pin "8") (pinfunction "V+_8") (pintype "power_in"))
      (node (ref "R41") (pin "2") (pinfunction "2_2") (pintype "passive"))
      (node (ref "X4") (pin "1") (pinfunction "1_1") (pintype "passive"))
    )
    (net (code "44") (name "DGND") (class "Default")
      (node (ref "C14") (pin "2") (pinfunction "2_2") (pintype "passive"))
      (node (ref "C15") (pin "1") (pinfunction "1_1") (pintype "passive"))
      (node (ref "C16") (pin "2") (pinfunction "2_2") (pintype "passive"))
      (node (ref "C17") (pin "1") (pinfunction "1_1") (pintype "passive"))
      (node (ref "C18") (pin "2") (pinfunction "2_2") (pintype "passive"))
      (node (ref "C19") (pin "1") (pinfunction "1_1") (pintype "passive"))
      (node (ref "C23") (pin "1") (pinfunction "1_1") (pintype "passive"))
      (node (ref "C24") (pin "1") (pinfunction "1_1") (pintype "passive"))
      (node (ref "C26") (pin "1") (pinfunction "1_1") (pintype "passive"))
      (node (ref "C28") (pin "1") (pinfunction "1_1") (pintype "passive"))
      (node (ref "C30") (pin "1") (pinfunction "1_1") (pintype "passive"))
      (node (ref "D3") (pin "16") (pinfunction "VSS_16") (pintype "passive"))
      (node (ref "D4") (pin "4") (pinfunction "GND_4") (pintype "power_in"))
      (node (ref "D4") (pin "5") (pinfunction "INB+_5") (pintype "input"))
      (node (ref "D4") (pin "6") (pinfunction "INB-_6") (pintype "input"))
      (node (ref "R40") (pin "1") (pinfunction "1_1") (pintype "passive"))
      (node (ref "R42") (pin "1") (pinfunction "1_1") (pintype "passive"))
      (node (ref "R47") (pin "2") (pinfunction "2_2") (pintype "passive"))
      (node (ref "TP12") (pin "1") (pinfunction "1_1") (pintype "passive"))
      (node (ref "VT2") (pin "1") (pinfunction "E_1") (pintype "passive"))
      (node (ref "VT3") (pin "1") (pinfunction "E_1") (pintype "passive"))
      (node (ref "VT4") (pin "1") (pinfunction "E_1") (pintype "passive"))
      (node (ref "X3") (pin "19") (pinfunction "19_19") (pintype "power_in"))
      (node (ref "X4") (pin "2") (pinfunction "2_2") (pintype "passive"))
    )
    (net (code "45") (name "GND") (class "Default")
      (node (ref "R44") (pin "2") (pinfunction "2_2") (pintype "passive"))
      (node (ref "R45") (pin "2") (pinfunction "2_2") (pintype "passive"))
      (node (ref "R46") (pin "2") (pinfunction "2_2") (pintype "passive"))
      (node (ref "R47") (pin "1") (pinfunction "1_1") (pintype "passive"))
      (node (ref "TP13") (pin "1") (pinfunction "1_1") (pintype "passive"))
    )
    (net (code "46") (name "Net-(C24-Pad2)") (class "Default")
      (node (ref "C24") (pin "2") (pinfunction "2_2") (pintype "passive"))
      (node (ref "R36") (pin "2") (pinfunction "2_2") (pintype "passive"))
      (node (ref "R37") (pin "2") (pinfunction "2_2") (pintype "passive"))
      (node (ref "R38") (pin "2") (pinfunction "2_2") (pintype "passive"))
      (node (ref "R39") (pin "1") (pinfunction "1_1") (pintype "passive"))
    )
    (net (code "47") (name "Net-(D3-HIN(U))") (class "Default")
      (node (ref "C14") (pin "1") (pinfunction "1_1") (pintype "passive"))
      (node (ref "D3") (pin "7") (pinfunction "HIN(U)_7") (pintype "passive"))
      (node (ref "R30") (pin "2") (pinfunction "2_2") (pintype "passive"))
      (node (ref "TP3") (pin "1") (pinfunction "1_1") (pintype "passive"))
    )
    (net (code "48") (name "Net-(D3-HIN(V))") (class "Default")
      (node (ref "C16") (pin "1") (pinfunction "1_1") (pintype "passive"))
      (node (ref "D3") (pin "8") (pinfunction "HIN(V)_8") (pintype "passive"))
      (node (ref "R31") (pin "2") (pinfunction "2_2") (pintype "passive"))
      (node (ref "TP5") (pin "1") (pinfunction "1_1") (pintype "passive"))
    )
    (net (code "49") (name "Net-(D3-HIN(W))") (class "Default")
      (node (ref "C18") (pin "1") (pinfunction "1_1") (pintype "passive"))
      (node (ref "D3") (pin "9") (pinfunction "HIN(W)_9") (pintype "passive"))
      (node (ref "R32") (pin "2") (pinfunction "2_2") (pintype "passive"))
      (node (ref "TP7") (pin "1") (pinfunction "1_1") (pintype "passive"))
    )
    (net (code "50") (name "Net-(D3-LIN(U))") (class "Default")
      (node (ref "C19") (pin "2") (pinfunction "2_2") (pintype "passive"))
      (node (ref "D3") (pin "10") (pinfunction "LIN(U)_10") (pintype "passive"))
      (node (ref "R33") (pin "2") (pinfunction "2_2") (pintype "passive"))
      (node (ref "TP8") (pin "1") (pinfunction "1_1") (pintype "passive"))
    )
    (net (code "51") (name "Net-(D3-LIN(V))") (class "Default")
      (node (ref "C17") (pin "2") (pinfunction "2_2") (pintype "passive"))
      (node (ref "D3") (pin "11") (pinfunction "LIN(V)_11") (pintype "passive"))
      (node (ref "R34") (pin "2") (pinfunction "2_2") (pintype "passive"))
      (node (ref "TP6") (pin "1") (pinfunction "1_1") (pintype "passive"))
    )
    (net (code "52") (name "Net-(D3-LIN(W))") (class "Default")
      (node (ref "C15") (pin "2") (pinfunction "2_2") (pintype "passive"))
      (node (ref "D3") (pin "12") (pinfunction "LIN(W)_12") (pintype "passive"))
      (node (ref "R35") (pin "2") (pinfunction "2_2") (pintype "passive"))
      (node (ref "TP4") (pin "1") (pinfunction "1_1") (pintype "passive"))
    )
    (net (code "53") (name "Net-(D3-U)") (class "Default")
      (node (ref "D3") (pin "22") (pinfunction "U_22") (pintype "passive"))
      (node (ref "TP14") (pin "1") (pinfunction "1_1") (pintype "passive"))
      (node (ref "X5") (pin "1") (pinfunction "1_1") (pintype "passive"))
    )
    (net (code "54") (name "Net-(D3-V)") (class "Default")
      (node (ref "D3") (pin "21") (pinfunction "V_21") (pintype "passive"))
      (node (ref "TP15") (pin "1") (pinfunction "1_1") (pintype "passive"))
      (node (ref "X5") (pin "2") (pinfunction "2_2") (pintype "passive"))
    )
    (net (code "55") (name "Net-(D3-VB(U))") (class "Default")
      (node (ref "C27") (pin "1") (pinfunction "1_1") (pintype "passive"))
      (node (ref "C29") (pin "1") (pinfunction "1_1") (pintype "passive"))
      (node (ref "D3") (pin "2") (pinfunction "VB(U)_2") (pintype "passive"))
    )
    (net (code "56") (name "Net-(D3-VB(V))") (class "Default")
      (node (ref "C22") (pin "1") (pinfunction "1_1") (pintype "passive"))
      (node (ref "C25") (pin "1") (pinfunction "1_1") (pintype "passive"))
      (node (ref "D3") (pin "4") (pinfunction "VB(V)_4") (pintype "passive"))
    )
    (net (code "57") (name "Net-(D3-VB(W))") (class "Default")
      (node (ref "C20") (pin "1") (pinfunction "1_1") (pintype "passive"))
      (node (ref "C21") (pin "1") (pinfunction "1_1") (pintype "passive"))
      (node (ref "D3") (pin "6") (pinfunction "VB(W)_6") (pintype "passive"))
    )
    (net (code "58") (name "Net-(D3-VS(U))") (class "Default")
      (node (ref "C27") (pin "2") (pinfunction "2_2") (pintype "passive"))
      (node (ref "C29") (pin "2") (pinfunction "2_2") (pintype "passive"))
      (node (ref "D3") (pin "1") (pinfunction "VS(U)_1") (pintype "passive"))
    )
    (net (code "59") (name "Net-(D3-VS(V))") (class "Default")
      (node (ref "C22") (pin "2") (pinfunction "2_2") (pintype "passive"))
      (node (ref "C25") (pin "2") (pinfunction "2_2") (pintype "passive"))
      (node (ref "D3") (pin "3") (pinfunction "VS(V)_3") (pintype "passive"))
    )
    (net (code "60") (name "Net-(D3-VS(W))") (class "Default")
      (node (ref "C20") (pin "2") (pinfunction "2_2") (pintype "passive"))
      (node (ref "C21") (pin "2") (pinfunction "2_2") (pintype "passive"))
      (node (ref "D3") (pin "5") (pinfunction "VS(W)_5") (pintype "passive"))
    )
    (net (code "61") (name "Net-(D3-W)") (class "Default")
      (node (ref "D3") (pin "20") (pinfunction "W_20") (pintype "passive"))
      (node (ref "TP16") (pin "1") (pinfunction "1_1") (pintype "passive"))
      (node (ref "X5") (pin "3") (pinfunction "3_3") (pintype "passive"))
    )
    (net (code "62") (name "Net-(D4A-INA-)") (class "Default")
      (node (ref "D4") (pin "2") (pinfunction "INA-_2") (pintype "input"))
      (node (ref "R41") (pin "1") (pinfunction "1_1") (pintype "passive"))
      (node (ref "R42") (pin "2") (pinfunction "2_2") (pintype "passive"))
      (node (ref "TP11") (pin "1") (pinfunction "1_1") (pintype "passive"))
    )
    (net (code "63") (name "Net-(VT2-B)") (class "Default")
      (node (ref "R19") (pin "2") (pinfunction "2_2") (pintype "passive"))
      (node (ref "VT2") (pin "2") (pinfunction "B_2") (pintype "passive"))
    )
    (net (code "64") (name "Net-(VT3-B)") (class "Default")
      (node (ref "R20") (pin "2") (pinfunction "2_2") (pintype "passive"))
      (node (ref "VT3") (pin "2") (pinfunction "B_2") (pintype "passive"))
    )
    (net (code "65") (name "Net-(VT4-B)") (class "Default")
      (node (ref "R21") (pin "2") (pinfunction "2_2") (pintype "passive"))
      (node (ref "VT4") (pin "2") (pinfunction "B_2") (pintype "passive"))
    )
    (net (code "66") (name "unconnected-(D3-NC-Pad24)") (class "Default")
      (node (ref "D3") (pin "24") (pinfunction "NC_24") (pintype "passive"))
    )
    (net (code "67") (name "unconnected-(D4B-OUTB-Pad7)") (class "Default")
      (node (ref "D4") (pin "7") (pinfunction "OUTB_7") (pintype "power_in"))
    )
    (net (code "68") (name "unconnected-(HG1-KA-Pad3)") (class "Default")
      (node (ref "HG1") (pin "3") (pinfunction "KA_3") (pintype "passive"))
    )
    (net (code "69") (name "unconnected-(HG2-KA-Pad3)") (class "Default")
      (node (ref "HG2") (pin "3") (pinfunction "KA_3") (pintype "passive"))
    )
    (net (code "70") (name "unconnected-(HG3-KA-Pad3)") (class "Default")
      (node (ref "HG3") (pin "3") (pinfunction "KA_3") (pintype "passive"))
    )
    (net (code "71") (name "unconnected-(X3-Pad1)") (class "Default")
      (node (ref "X3") (pin "1") (pinfunction "1_1") (pintype "passive"))
    )
    (net (code "72") (name "unconnected-(X3-Pad13)") (class "Default")
      (node (ref "X3") (pin "13") (pinfunction "13_13") (pintype "power_in"))
    )
    (net (code "73") (name "unconnected-(X3-Pad14)") (class "Default")
      (node (ref "X3") (pin "14") (pinfunction "14_14") (pintype "power_in"))
    )
    (net (code "74") (name "unconnected-(X3-Pad15)") (class "Default")
      (node (ref "X3") (pin "15") (pinfunction "15_15") (pintype "power_in"))
    )
    (net (code "75") (name "unconnected-(X3-Pad16)") (class "Default")
      (node (ref "X3") (pin "16") (pinfunction "16_16") (pintype "power_in"))
    )
    (net (code "76") (name "unconnected-(X3-Pad20)") (class "Default")
      (node (ref "X3") (pin "20") (pinfunction "20_20") (pintype "power_in"))
    )
    (net (code "77") (name "unconnected-(X4-Pad15)") (class "Default")
      (node (ref "X4") (pin "15") (pinfunction "15_15") (pintype "power_in"))
    )
    (net (code "78") (name "unconnected-(X4-Pad16)") (class "Default")
      (node (ref "X4") (pin "16") (pinfunction "16_16") (pintype "power_in"))
    )
    (net (code "79") (name "unconnected-(X4-Pad17)") (class "Default")
      (node (ref "X4") (pin "17") (pinfunction "17_17") (pintype "power_in"))
    )
    (net (code "80") (name "unconnected-(X4-Pad18)") (class "Default")
      (node (ref "X4") (pin "18") (pinfunction "18_18") (pintype "power_in"))
    )
    (net (code "81") (name "unconnected-(X4-Pad19)") (class "Default")
      (node (ref "X4") (pin "19") (pinfunction "19_19") (pintype "power_in"))
    )
    (net (code "82") (name "unconnected-(X4-Pad20)") (class "Default")
      (node (ref "X4") (pin "20") (pinfunction "20_20") (pintype "power_in"))
    )
  )
)
